# SM1.net
KiCad netlist of a schematic drawn in Altium Designer
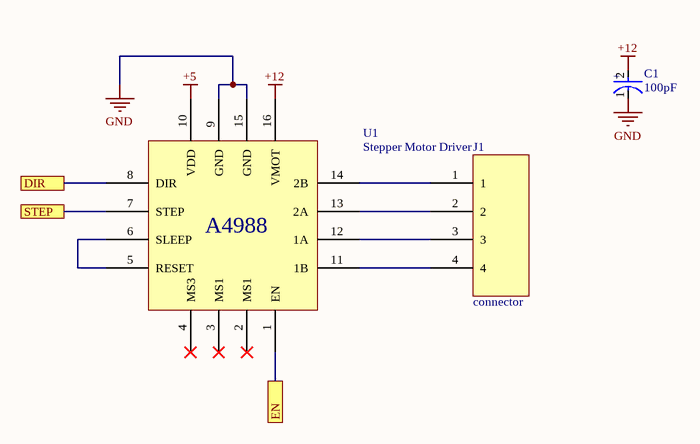
[diagram p0: SM1.SchDoc]

(export (version "E")
  (design (tool "Eeschema 10.0.6"))
  (components
    (comp (ref "C1")
      (value "100pF")
      (footprint "FP-SC-MFG")
      (description "CAP ALUM 10UF 20% 35V SMD")
      (fields (field (name "TOLERANCE") "20%") (field (name "VOLTAGE") "35V"))
      (libsource (lib "Altium Content Vault") (part "203bc49f2ac43e59fd269a8c329ed05"))
    )
    (comp (ref "J1") (value "connector") (footprint "JST_4P") (libsource (lib "Schlib") (part "JST_4P")))
    (comp (ref "U1")
      (value "Stepper Motor Driver")
      (footprint "A4988")
      (libsource (lib "Schlib") (part "A4988"))
    )
  )
  (nets
    (net (code "1") (name "+5") (class "Default")
      (node (ref "U1") (pin "10") (pinfunction "VDD_10") (pintype "passive"))
    )
    (net (code "2") (name "+12") (class "Default")
      (node (ref "C1") (pin "2") (pinfunction "A_2") (pintype "passive"))
      (node (ref "U1") (pin "16") (pinfunction "VMOT_16") (pintype "passive"))
    )
    (net (code "3") (name "/DIR") (class "Default")
      (node (ref "U1") (pin "8") (pinfunction "DIR_8") (pintype "passive"))
    )
    (net (code "4") (name "/EN") (class "Default")
      (node (ref "U1") (pin "1") (pinfunction "EN_1") (pintype "passive"))
    )
    (net (code "5") (name "/STEP") (class "Default")
      (node (ref "U1") (pin "7") (pinfunction "STEP_7") (pintype "passive"))
    )
    (net (code "6") (name "GND") (class "Default")
      (node (ref "C1") (pin "1") (pinfunction "C_1") (pintype "passive"))
      (node (ref "U1") (pin "15") (pinfunction "GND_15") (pintype "passive"))
      (node (ref "U1") (pin "9") (pinfunction "GND_9") (pintype "passive"))
    )
    (net (code "7") (name "Net-(U1-1A)") (class "Default")
      (node (ref "J1") (pin "3") (pinfunction "3_3") (pintype "passive"))
      (node (ref "U1") (pin "12") (pinfunction "1A_12") (pintype "passive"))
    )
    (net (code "8") (name "Net-(U1-1B)") (class "Default")
      (node (ref "J1") (pin "4") (pinfunction "4_4") (pintype "passive"))
      (node (ref "U1") (pin "11") (pinfunction "1B_11") (pintype "passive"))
    )
    (net (code "9") (name "Net-(U1-2A)") (class "Default")
      (node (ref "J1") (pin "2") (pinfunction "2_2") (pintype "passive"))
      (node (ref "U1") (pin "13") (pinfunction "2A_13") (pintype "passive"))
    )
    (net (code "10") (name "Net-(U1-2B)") (class "Default")
      (node (ref "J1") (pin "1") (pinfunction "1_1") (pintype "passive"))
      (node (ref "U1") (pin "14") (pinfunction "2B_14") (pintype "passive"))
    )
    (net (code "11") (name "Net-(U1-RESET)") (class "Default")
      (node (ref "U1") (pin "5") (pinfunction "RESET_5") (pintype "passive"))
      (node (ref "U1") (pin "6") (pinfunction "SLEEP_6") (pintype "passive"))
    )
    (net (code "12") (name "unconnected-(U1-MS1-Pad2)") (class "Default")
      (node (ref "U1") (pin "2") (pinfunction "MS1_2") (pintype "passive+no_connect"))
    )
    (net (code "13") (name "unconnected-(U1-MS1-Pad3)") (class "Default")
      (node (ref "U1") (pin "3") (pinfunction "MS1_3") (pintype "passive+no_connect"))
    )
    (net (code "14") (name "unconnected-(U1-MS3-Pad4)") (class "Default")
      (node (ref "U1") (pin "4") (pinfunction "MS3_4") (pintype "passive+no_connect"))
    )
  )
)
